# Bluetooth.net
KiCad netlist of a schematic drawn in Altium Designer
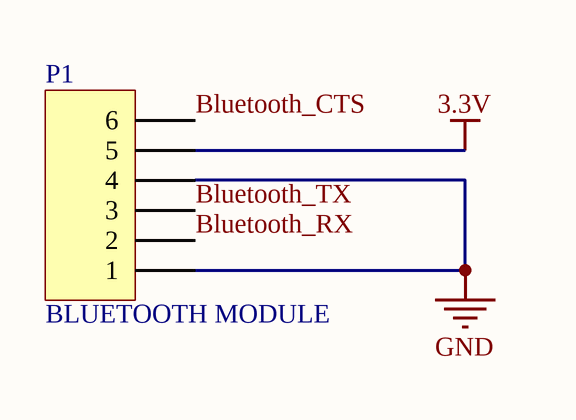
[diagram p0: Bluetooth.SchDoc]

(export (version "E")
  (design (tool "Eeschema 10.0.6"))
  (components
    (comp (ref "P1")
      (value "BLUETOOTH MODULE")
      (footprint "HDR1X6")
      (description "Header, 6-Pin")
      (fields (field (name "PUBLISHER") "Altium Limited"))
      (libsource (lib "Miscellaneous Connectors") (part "Header 6"))
    )
  )
  (nets
    (net (code "1") (name "/Bluetooth_CTS") (class "Default")
      (node (ref "P1") (pin "6") (pinfunction "6_6") (pintype "passive"))
    )
    (net (code "2") (name "/Bluetooth_RX") (class "Default")
      (node (ref "P1") (pin "2") (pinfunction "2_2") (pintype "passive"))
    )
    (net (code "3") (name "/Bluetooth_TX") (class "Default")
      (node (ref "P1") (pin "3") (pinfunction "3_3") (pintype "passive"))
    )
    (net (code "4") (name "3.3V") (class "Default")
      (node (ref "P1") (pin "5") (pinfunction "5_5") (pintype "passive"))
    )
    (net (code "5") (name "GND") (class "Default")
      (node (ref "P1") (pin "1") (pinfunction "1_1") (pintype "passive"))
      (node (ref "P1") (pin "4") (pinfunction "4_4") (pintype "passive"))
    )
  )
)
